# ECE445_Interrogator_Schematic_FINAL.net
KiCad netlist of a schematic drawn in EAGLE
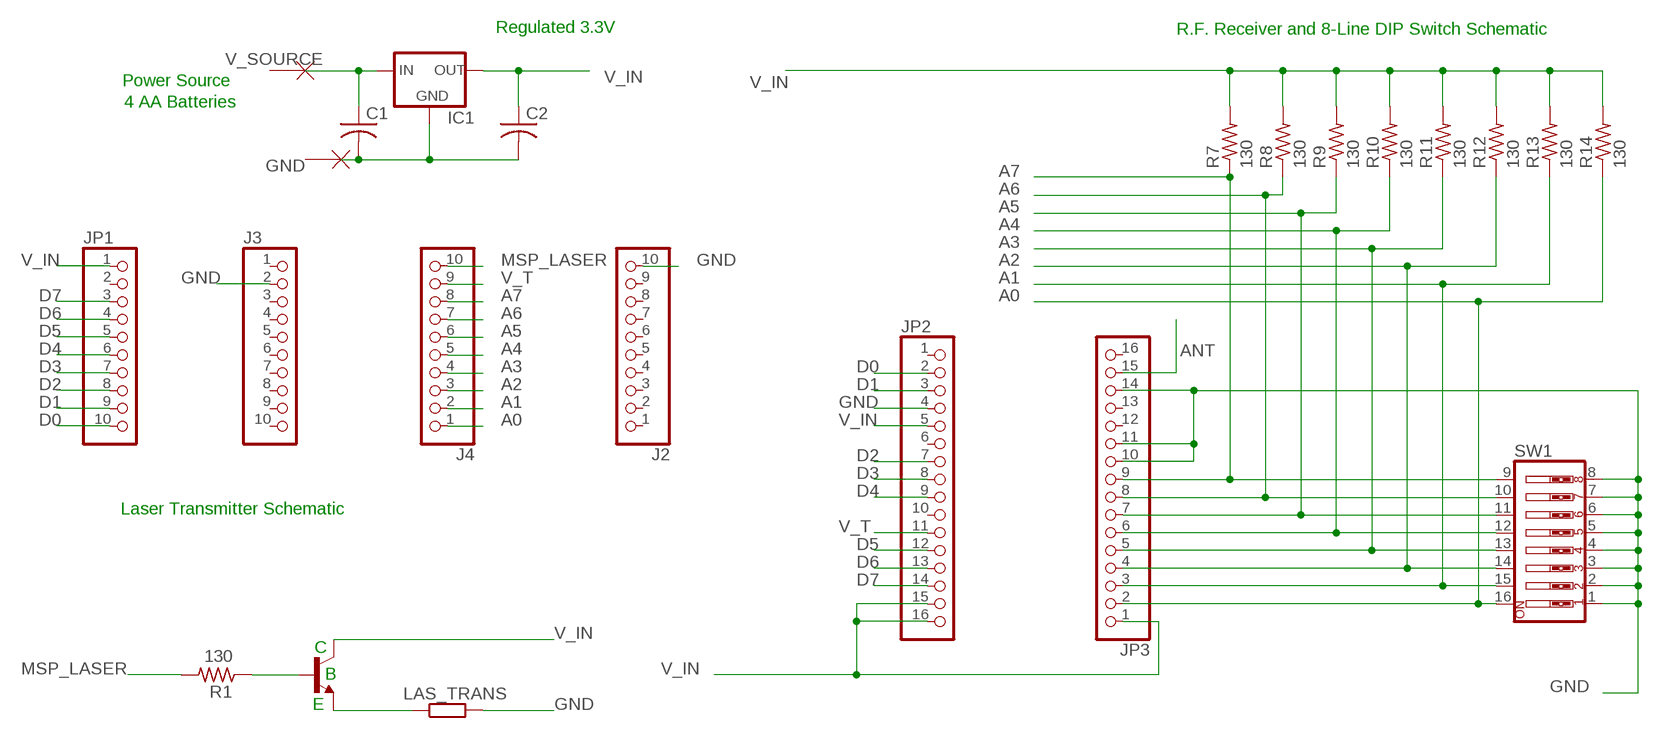
[diagram p0: schematic, sheet 1]

(export (version "E")
  (design (tool "Eeschema 10.0.6"))
  (components
    (comp (ref "C1")
      (value "C-US050-025X075")
      (footprint "eagle-import:C050-025X075")
      (libsource (lib "eagle-import") (part "C-US050-025X075"))
    )
    (comp (ref "C2")
      (value "C-US050-025X075")
      (footprint "eagle-import:C050-025X075")
      (libsource (lib "eagle-import") (part "C-US050-025X075"))
    )
    (comp (ref "IC1")
      (value "78LXX")
      (footprint "eagle-import:78LXX")
      (libsource (lib "eagle-import") (part "78LXX"))
    )
    (comp (ref "J2")
      (value "PINHD-1X10")
      (footprint "eagle-import:1X10")
      (libsource (lib "eagle-import") (part "PINHD-1X10"))
    )
    (comp (ref "J3")
      (value "PINHD-1X10")
      (footprint "eagle-import:1X10")
      (libsource (lib "eagle-import") (part "PINHD-1X10"))
    )
    (comp (ref "J4")
      (value "PINHD-1X10")
      (footprint "eagle-import:1X10")
      (libsource (lib "eagle-import") (part "PINHD-1X10"))
    )
    (comp (ref "JP1")
      (value "PINHD-1X10")
      (footprint "eagle-import:1X10")
      (libsource (lib "eagle-import") (part "PINHD-1X10"))
    )
    (comp (ref "JP2")
      (value "PINHD-1X16")
      (footprint "eagle-import:1X16")
      (libsource (lib "eagle-import") (part "PINHD-1X16"))
    )
    (comp (ref "JP3")
      (value "PINHD-1X16")
      (footprint "eagle-import:1X16")
      (libsource (lib "eagle-import") (part "PINHD-1X16"))
    )
    (comp (ref "LAS_TRANS")
      (value "R-EU_0204/5")
      (footprint "eagle-import:0204_5")
      (libsource (lib "eagle-import") (part "R-EU_0204/5"))
    )
    (comp (ref "Q2")
      (value "BC338")
      (footprint "eagle-import:TO92-EBC")
      (libsource (lib "eagle-import") (part "BC338"))
    )
    (comp (ref "R1")
      (value "130")
      (footprint "eagle-import:0204_5")
      (libsource (lib "eagle-import") (part "R-US_0204/5"))
    )
    (comp (ref "R7")
      (value "130")
      (footprint "eagle-import:0204_5")
      (libsource (lib "eagle-import") (part "R-US_0204/5"))
    )
    (comp (ref "R8")
      (value "130")
      (footprint "eagle-import:0204_5")
      (libsource (lib "eagle-import") (part "R-US_0204/5"))
    )
    (comp (ref "R9")
      (value "130")
      (footprint "eagle-import:0204_5")
      (libsource (lib "eagle-import") (part "R-US_0204/5"))
    )
    (comp (ref "R10")
      (value "130")
      (footprint "eagle-import:0204_5")
      (libsource (lib "eagle-import") (part "R-US_0204/5"))
    )
    (comp (ref "R11")
      (value "130")
      (footprint "eagle-import:0204_5")
      (libsource (lib "eagle-import") (part "R-US_0204/5"))
    )
    (comp (ref "R12")
      (value "130")
      (footprint "eagle-import:0204_5")
      (libsource (lib "eagle-import") (part "R-US_0204/5"))
    )
    (comp (ref "R13")
      (value "130")
      (footprint "eagle-import:0204_5")
      (libsource (lib "eagle-import") (part "R-US_0204/5"))
    )
    (comp (ref "R14")
      (value "130")
      (footprint "eagle-import:0204_5")
      (libsource (lib "eagle-import") (part "R-US_0204/5"))
    )
    (comp (ref "SW1")
      (value "SW_DIP-8")
      (footprint "eagle-import:EDG-08")
      (libsource (lib "eagle-import") (part "SW_DIP-8"))
    )
    (comp (ref "U$1")
      (value "NO_CONNECT")
      (footprint "eagle-import:NO_CONNECT")
      (libsource (lib "eagle-import") (part "NO_CONNECT"))
    )
    (comp (ref "U$2")
      (value "NO_CONNECT")
      (footprint "eagle-import:NO_CONNECT")
      (libsource (lib "eagle-import") (part "NO_CONNECT"))
    )
  )
  (nets
    (net (code "1") (name "/A0") (class "Default")
      (node (ref "J4") (pin "1") (pinfunction "1_1") (pintype "passive"))
      (node (ref "JP3") (pin "2") (pinfunction "2_2") (pintype "passive"))
      (node (ref "R14") (pin "1") (pinfunction "1_1") (pintype "passive"))
      (node (ref "SW1") (pin "16") (pinfunction "16_16") (pintype "passive"))
    )
    (net (code "2") (name "/A1") (class "Default")
      (node (ref "J4") (pin "2") (pinfunction "2_2") (pintype "passive"))
      (node (ref "JP3") (pin "3") (pinfunction "3_3") (pintype "passive"))
      (node (ref "R13") (pin "1") (pinfunction "1_1") (pintype "passive"))
      (node (ref "SW1") (pin "15") (pinfunction "15_15") (pintype "passive"))
    )
    (net (code "3") (name "/A2") (class "Default")
      (node (ref "J4") (pin "3") (pinfunction "3_3") (pintype "passive"))
      (node (ref "JP3") (pin "4") (pinfunction "4_4") (pintype "passive"))
      (node (ref "R12") (pin "1") (pinfunction "1_1") (pintype "passive"))
      (node (ref "SW1") (pin "14") (pinfunction "14_14") (pintype "passive"))
    )
    (net (code "4") (name "/A3") (class "Default")
      (node (ref "J4") (pin "4") (pinfunction "4_4") (pintype "passive"))
      (node (ref "JP3") (pin "5") (pinfunction "5_5") (pintype "passive"))
      (node (ref "R11") (pin "1") (pinfunction "1_1") (pintype "passive"))
      (node (ref "SW1") (pin "13") (pinfunction "13_13") (pintype "passive"))
    )
    (net (code "5") (name "/A4") (class "Default")
      (node (ref "J4") (pin "5") (pinfunction "5_5") (pintype "passive"))
      (node (ref "JP3") (pin "6") (pinfunction "6_6") (pintype "passive"))
      (node (ref "R10") (pin "1") (pinfunction "1_1") (pintype "passive"))
      (node (ref "SW1") (pin "12") (pinfunction "12_12") (pintype "passive"))
    )
    (net (code "6") (name "/A5") (class "Default")
      (node (ref "J4") (pin "6") (pinfunction "6_6") (pintype "passive"))
      (node (ref "JP3") (pin "7") (pinfunction "7_7") (pintype "passive"))
      (node (ref "R9") (pin "1") (pinfunction "1_1") (pintype "passive"))
      (node (ref "SW1") (pin "11") (pinfunction "11_11") (pintype "passive"))
    )
    (net (code "7") (name "/A6") (class "Default")
      (node (ref "J4") (pin "7") (pinfunction "7_7") (pintype "passive"))
      (node (ref "JP3") (pin "8") (pinfunction "8_8") (pintype "passive"))
      (node (ref "R8") (pin "1") (pinfunction "1_1") (pintype "passive"))
      (node (ref "SW1") (pin "10") (pinfunction "10_10") (pintype "passive"))
    )
    (net (code "8") (name "/A7") (class "Default")
      (node (ref "J4") (pin "8") (pinfunction "8_8") (pintype "passive"))
      (node (ref "JP3") (pin "9") (pinfunction "9_9") (pintype "passive"))
      (node (ref "R7") (pin "1") (pinfunction "1_1") (pintype "passive"))
      (node (ref "SW1") (pin "9") (pinfunction "9_9") (pintype "passive"))
    )
    (net (code "9") (name "/ANT") (class "Default")
      (node (ref "JP3") (pin "15") (pinfunction "15_15") (pintype "passive"))
    )
    (net (code "10") (name "/D0") (class "Default")
      (node (ref "JP1") (pin "10") (pinfunction "10_10") (pintype "passive"))
      (node (ref "JP2") (pin "2") (pinfunction "2_2") (pintype "passive"))
    )
    (net (code "11") (name "/D1") (class "Default")
      (node (ref "JP1") (pin "9") (pinfunction "9_9") (pintype "passive"))
      (node (ref "JP2") (pin "3") (pinfunction "3_3") (pintype "passive"))
    )
    (net (code "12") (name "/D2") (class "Default")
      (node (ref "JP1") (pin "8") (pinfunction "8_8") (pintype "passive"))
      (node (ref "JP2") (pin "7") (pinfunction "7_7") (pintype "passive"))
    )
    (net (code "13") (name "/D3") (class "Default")
      (node (ref "JP1") (pin "7") (pinfunction "7_7") (pintype "passive"))
      (node (ref "JP2") (pin "8") (pinfunction "8_8") (pintype "passive"))
    )
    (net (code "14") (name "/D4") (class "Default")
      (node (ref "JP1") (pin "6") (pinfunction "6_6") (pintype "passive"))
      (node (ref "JP2") (pin "9") (pinfunction "9_9") (pintype "passive"))
    )
    (net (code "15") (name "/D5") (class "Default")
      (node (ref "JP1") (pin "5") (pinfunction "5_5") (pintype "passive"))
      (node (ref "JP2") (pin "12") (pinfunction "12_12") (pintype "passive"))
    )
    (net (code "16") (name "/D6") (class "Default")
      (node (ref "JP1") (pin "4") (pinfunction "4_4") (pintype "passive"))
      (node (ref "JP2") (pin "13") (pinfunction "13_13") (pintype "passive"))
    )
    (net (code "17") (name "/D7") (class "Default")
      (node (ref "JP1") (pin "3") (pinfunction "3_3") (pintype "passive"))
      (node (ref "JP2") (pin "14") (pinfunction "14_14") (pintype "passive"))
    )
    (net (code "18") (name "/GND") (class "Default")
      (node (ref "C1") (pin "2") (pinfunction "2_2") (pintype "passive"))
      (node (ref "C2") (pin "2") (pinfunction "2_2") (pintype "passive"))
      (node (ref "IC1") (pin "GND") (pinfunction "GND_GND") (pintype "input"))
      (node (ref "J2") (pin "10") (pinfunction "10_10") (pintype "passive"))
      (node (ref "J3") (pin "2") (pinfunction "2_2") (pintype "passive"))
      (node (ref "JP2") (pin "4") (pinfunction "4_4") (pintype "passive"))
      (node (ref "JP3") (pin "10") (pinfunction "10_10") (pintype "passive"))
      (node (ref "JP3") (pin "11") (pinfunction "11_11") (pintype "passive"))
      (node (ref "JP3") (pin "14") (pinfunction "14_14") (pintype "passive"))
      (node (ref "LAS_TRANS") (pin "2") (pinfunction "2_2") (pintype "passive"))
      (node (ref "SW1") (pin "1") (pinfunction "1_1") (pintype "passive"))
      (node (ref "SW1") (pin "2") (pinfunction "2_2") (pintype "passive"))
      (node (ref "SW1") (pin "3") (pinfunction "3_3") (pintype "passive"))
      (node (ref "SW1") (pin "4") (pinfunction "4_4") (pintype "passive"))
      (node (ref "SW1") (pin "5") (pinfunction "5_5") (pintype "passive"))
      (node (ref "SW1") (pin "6") (pinfunction "6_6") (pintype "passive"))
      (node (ref "SW1") (pin "7") (pinfunction "7_7") (pintype "passive"))
      (node (ref "SW1") (pin "8") (pinfunction "8_8") (pintype "passive"))
      (node (ref "U$1") (pin "P$1") (pinfunction "NC_P$1") (pintype "bidirectional"))
    )
    (net (code "19") (name "/MSP_LASER") (class "Default")
      (node (ref "J4") (pin "10") (pinfunction "10_10") (pintype "passive"))
      (node (ref "R1") (pin "2") (pinfunction "2_2") (pintype "passive"))
    )
    (net (code "20") (name "/V_IN") (class "Default")
      (node (ref "C2") (pin "1") (pinfunction "1_1") (pintype "passive"))
      (node (ref "IC1") (pin "OUT") (pinfunction "OUT_OUT") (pintype "passive"))
      (node (ref "JP1") (pin "1") (pinfunction "1_1") (pintype "passive"))
      (node (ref "JP2") (pin "15") (pinfunction "15_15") (pintype "passive"))
      (node (ref "JP2") (pin "16") (pinfunction "16_16") (pintype "passive"))
      (node (ref "JP2") (pin "5") (pinfunction "5_5") (pintype "passive"))
      (node (ref "JP3") (pin "1") (pinfunction "1_1") (pintype "passive"))
      (node (ref "Q2") (pin "C") (pinfunction "C_C") (pintype "passive"))
      (node (ref "R10") (pin "2") (pinfunction "2_2") (pintype "passive"))
      (node (ref "R11") (pin "2") (pinfunction "2_2") (pintype "passive"))
      (node (ref "R12") (pin "2") (pinfunction "2_2") (pintype "passive"))
      (node (ref "R13") (pin "2") (pinfunction "2_2") (pintype "passive"))
      (node (ref "R14") (pin "2") (pinfunction "2_2") (pintype "passive"))
      (node (ref "R7") (pin "2") (pinfunction "2_2") (pintype "passive"))
      (node (ref "R8") (pin "2") (pinfunction "2_2") (pintype "passive"))
      (node (ref "R9") (pin "2") (pinfunction "2_2") (pintype "passive"))
    )
    (net (code "21") (name "/V_SOURCE") (class "Default")
      (node (ref "C1") (pin "1") (pinfunction "1_1") (pintype "passive"))
      (node (ref "IC1") (pin "IN") (pinfunction "IN_IN") (pintype "input"))
      (node (ref "U$2") (pin "P$1") (pinfunction "NC_P$1") (pintype "bidirectional"))
    )
    (net (code "22") (name "/V_T") (class "Default")
      (node (ref "J4") (pin "9") (pinfunction "9_9") (pintype "passive"))
      (node (ref "JP2") (pin "11") (pinfunction "11_11") (pintype "passive"))
    )
    (net (code "23") (name "Net-(LAS_TRANS-Pad1)") (class "Default")
      (node (ref "LAS_TRANS") (pin "1") (pinfunction "1_1") (pintype "passive"))
      (node (ref "Q2") (pin "E") (pinfunction "E_E") (pintype "passive"))
    )
    (net (code "24") (name "Net-(Q2-PadB)") (class "Default")
      (node (ref "Q2") (pin "B") (pinfunction "B_B") (pintype "passive"))
      (node (ref "R1") (pin "1") (pinfunction "1_1") (pintype "passive"))
    )
    (net (code "25") (name "unconnected-(J2-Pad1)") (class "Default")
      (node (ref "J2") (pin "1") (pinfunction "1_1") (pintype "passive"))
    )
    (net (code "26") (name "unconnected-(J2-Pad2)") (class "Default")
      (node (ref "J2") (pin "2") (pinfunction "2_2") (pintype "passive"))
    )
    (net (code "27") (name "unconnected-(J2-Pad3)") (class "Default")
      (node (ref "J2") (pin "3") (pinfunction "3_3") (pintype "passive"))
    )
    (net (code "28") (name "unconnected-(J2-Pad4)") (class "Default")
      (node (ref "J2") (pin "4") (pinfunction "4_4") (pintype "passive"))
    )
    (net (code "29") (name "unconnected-(J2-Pad5)") (class "Default")
      (node (ref "J2") (pin "5") (pinfunction "5_5") (pintype "passive"))
    )
    (net (code "30") (name "unconnected-(J2-Pad6)") (class "Default")
      (node (ref "J2") (pin "6") (pinfunction "6_6") (pintype "passive"))
    )
    (net (code "31") (name "unconnected-(J2-Pad7)") (class "Default")
      (node (ref "J2") (pin "7") (pinfunction "7_7") (pintype "passive"))
    )
    (net (code "32") (name "unconnected-(J2-Pad8)") (class "Default")
      (node (ref "J2") (pin "8") (pinfunction "8_8") (pintype "passive"))
    )
    (net (code "33") (name "unconnected-(J2-Pad9)") (class "Default")
      (node (ref "J2") (pin "9") (pinfunction "9_9") (pintype "passive"))
    )
    (net (code "34") (name "unconnected-(J3-Pad1)") (class "Default")
      (node (ref "J3") (pin "1") (pinfunction "1_1") (pintype "passive"))
    )
    (net (code "35") (name "unconnected-(J3-Pad3)") (class "Default")
      (node (ref "J3") (pin "3") (pinfunction "3_3") (pintype "passive"))
    )
    (net (code "36") (name "unconnected-(J3-Pad4)") (class "Default")
      (node (ref "J3") (pin "4") (pinfunction "4_4") (pintype "passive"))
    )
    (net (code "37") (name "unconnected-(J3-Pad5)") (class "Default")
      (node (ref "J3") (pin "5") (pinfunction "5_5") (pintype "passive"))
    )
    (net (code "38") (name "unconnected-(J3-Pad6)") (class "Default")
      (node (ref "J3") (pin "6") (pinfunction "6_6") (pintype "passive"))
    )
    (net (code "39") (name "unconnected-(J3-Pad7)") (class "Default")
      (node (ref "J3") (pin "7") (pinfunction "7_7") (pintype "passive"))
    )
    (net (code "40") (name "unconnected-(J3-Pad8)") (class "Default")
      (node (ref "J3") (pin "8") (pinfunction "8_8") (pintype "passive"))
    )
    (net (code "41") (name "unconnected-(J3-Pad9)") (class "Default")
      (node (ref "J3") (pin "9") (pinfunction "9_9") (pintype "passive"))
    )
    (net (code "42") (name "unconnected-(J3-Pad10)") (class "Default")
      (node (ref "J3") (pin "10") (pinfunction "10_10") (pintype "passive"))
    )
    (net (code "43") (name "unconnected-(JP1-Pad2)") (class "Default")
      (node (ref "JP1") (pin "2") (pinfunction "2_2") (pintype "passive"))
    )
    (net (code "44") (name "unconnected-(JP2-Pad1)") (class "Default")
      (node (ref "JP2") (pin "1") (pinfunction "1_1") (pintype "passive"))
    )
    (net (code "45") (name "unconnected-(JP2-Pad6)") (class "Default")
      (node (ref "JP2") (pin "6") (pinfunction "6_6") (pintype "passive"))
    )
    (net (code "46") (name "unconnected-(JP2-Pad10)") (class "Default")
      (node (ref "JP2") (pin "10") (pinfunction "10_10") (pintype "passive"))
    )
    (net (code "47") (name "unconnected-(JP3-Pad12)") (class "Default")
      (node (ref "JP3") (pin "12") (pinfunction "12_12") (pintype "passive"))
    )
    (net (code "48") (name "unconnected-(JP3-Pad13)") (class "Default")
      (node (ref "JP3") (pin "13") (pinfunction "13_13") (pintype "passive"))
    )
    (net (code "49") (name "unconnected-(JP3-Pad16)") (class "Default")
      (node (ref "JP3") (pin "16") (pinfunction "16_16") (pintype "passive"))
    )
  )
)
